# V1_input_channel_noNegSply_sch.net
KiCad netlist of a schematic drawn in Altium Designer
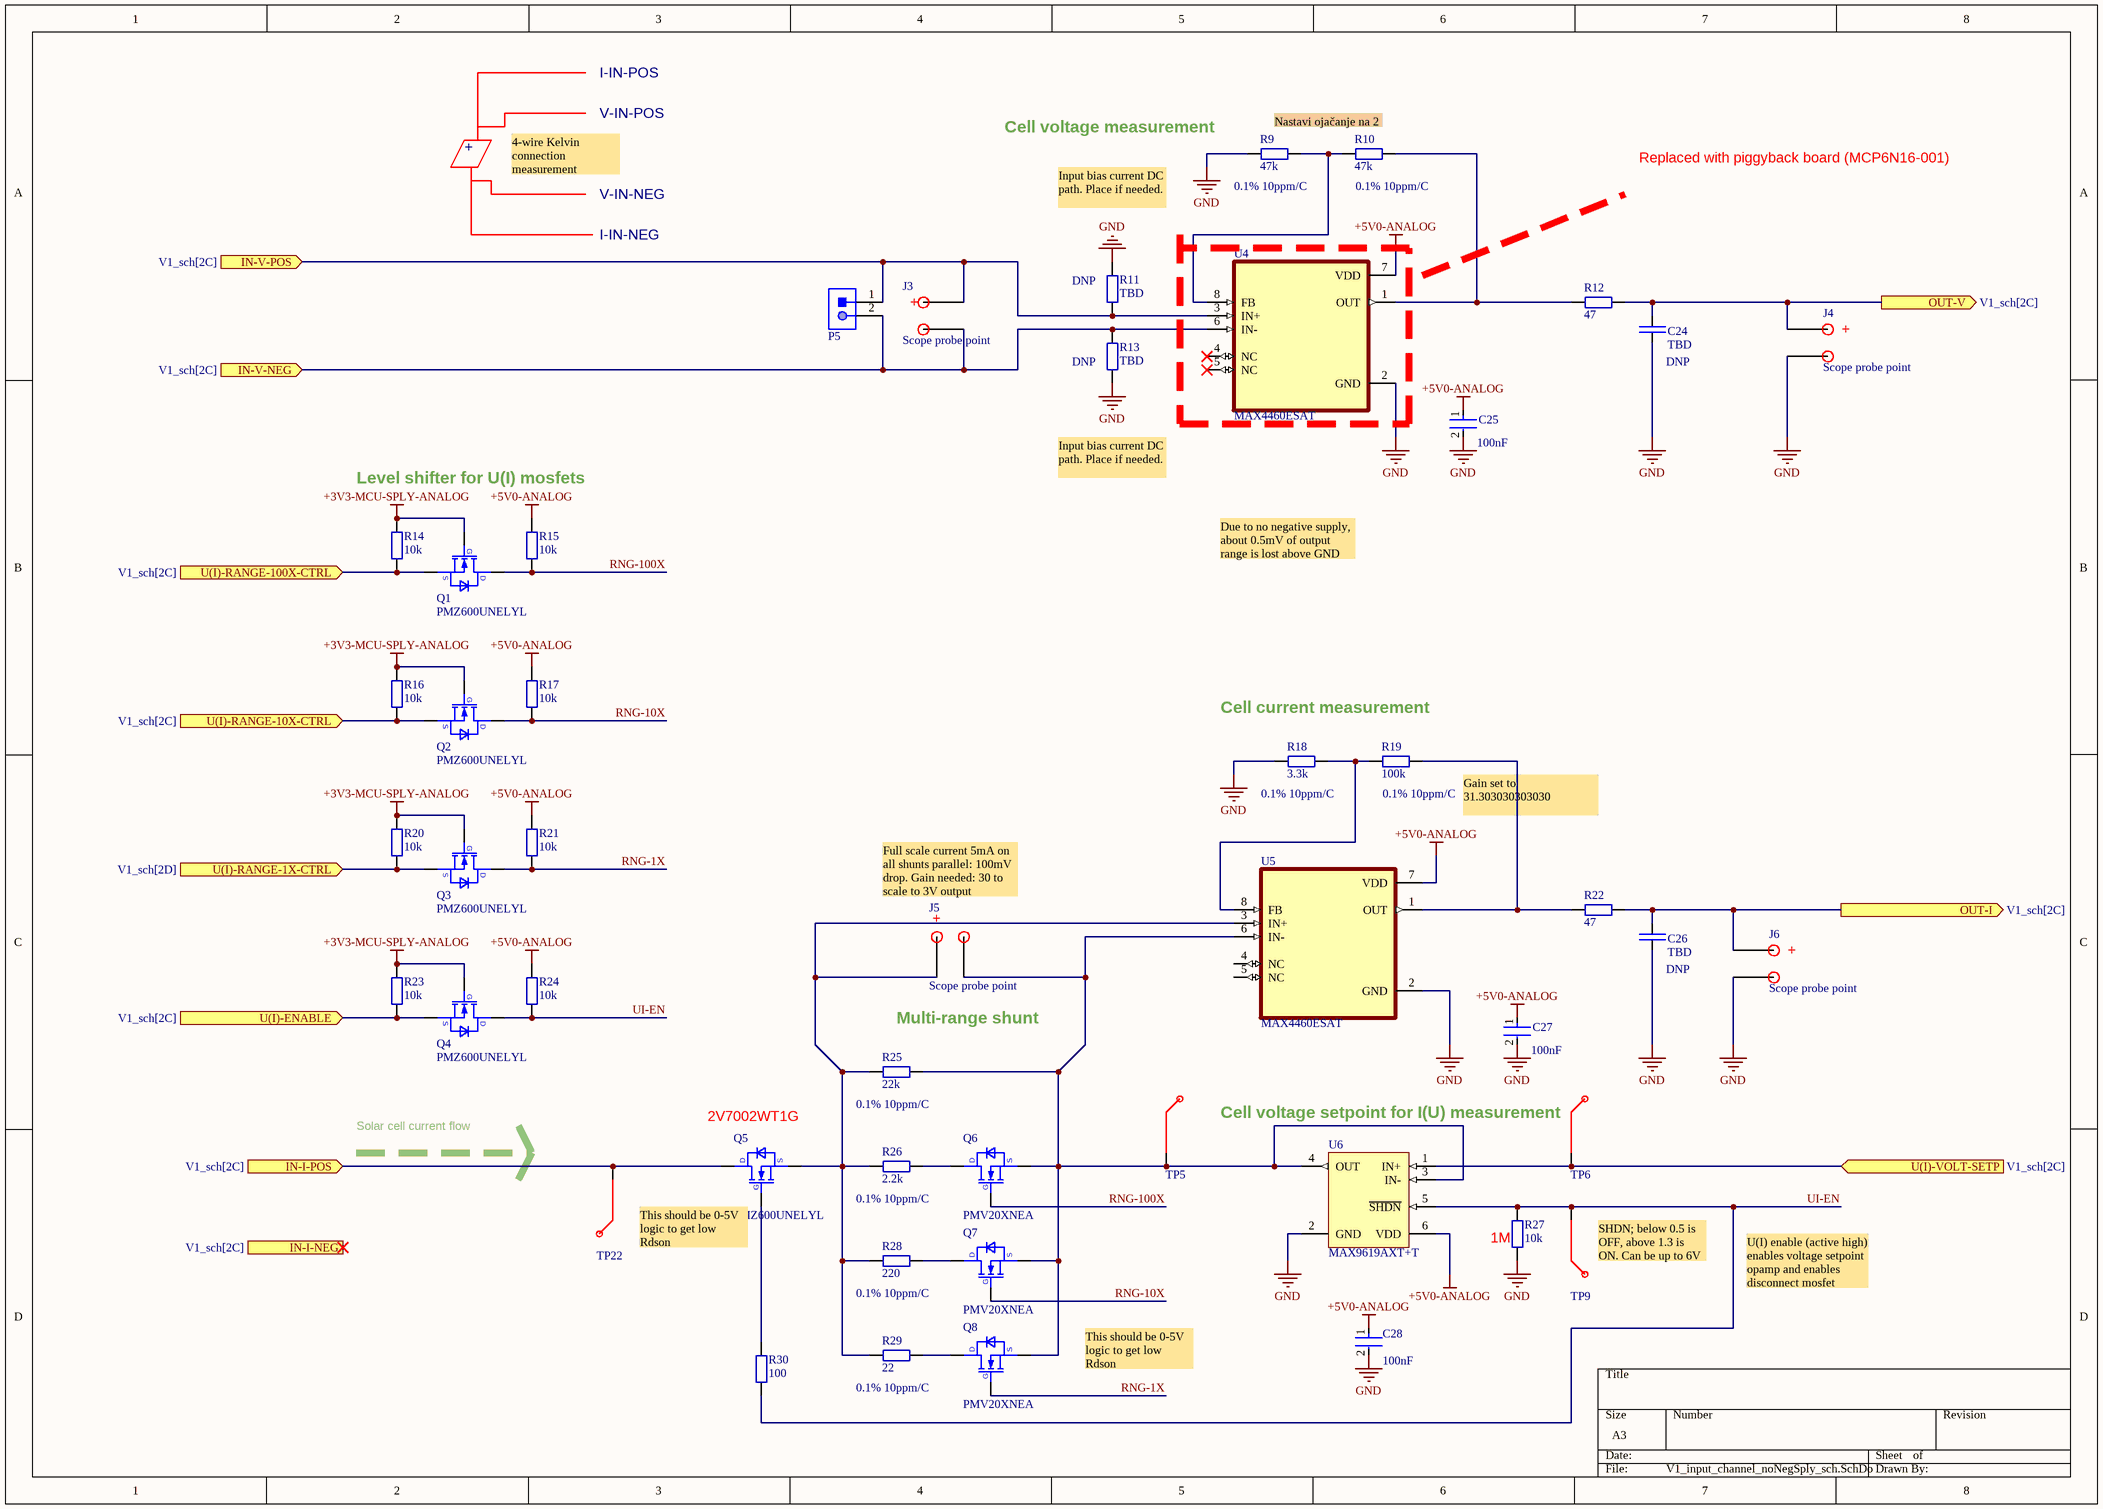
[diagram p0: V1_input_channel_noNegSply_sch.SchDoc]

(export (version "E")
  (design (tool "Eeschema 10.0.6"))
  (components
    (comp (ref "C24")
      (value "TBD")
      (footprint "Passives:FPR_0603_C_R0")
      (description "Capacitor - generic SMD")
      (fields (field (name "DNP") "DNP") (field (name "Comment") "PN_C0603_TBD"))
      (libsource (lib "Passives") (part "C"))
    )
    (comp (ref "C25")
      (value "885012206095")
      (footprint "FP-885012206095-IPC_B")
      (description "CAP CER 0.1UF 50V X7R 0603")
      (fields (field (name "TOLERANCE") "10%") (field (name "CAPACITANCE") "100nF"))
      (libsource (lib "Altium Content Vault") (part "11868f565c42a9108669ba33697ecf6"))
    )
    (comp (ref "C26")
      (value "TBD")
      (footprint "Passives:FPR_0603_C_R0")
      (description "Capacitor - generic SMD")
      (fields (field (name "DNP") "DNP") (field (name "Comment") "PN_C0603_TBD"))
      (libsource (lib "Passives") (part "C"))
    )
    (comp (ref "C27")
      (value "885012206095")
      (footprint "FP-885012206095-IPC_B")
      (description "CAP CER 0.1UF 50V X7R 0603")
      (fields (field (name "TOLERANCE") "10%") (field (name "CAPACITANCE") "100nF"))
      (libsource (lib "Altium Content Vault") (part "11868f565c42a9108669ba33697ecf6"))
    )
    (comp (ref "C28")
      (value "885012206095")
      (footprint "FP-885012206095-IPC_B")
      (description "CAP CER 0.1UF 50V X7R 0603")
      (fields (field (name "TOLERANCE") "10%") (field (name "CAPACITANCE") "100nF"))
      (libsource (lib "Altium Content Vault") (part "11868f565c42a9108669ba33697ecf6"))
    )
    (comp (ref "J3")
      (value "Scope probe point")
      (footprint "scope with ground spring probe point")
      (libsource (lib "") (part "Scope probe point_1"))
    )
    (comp (ref "J4")
      (value "Scope probe point")
      (footprint "scope with ground spring probe point")
      (libsource (lib "planinsekLib_sch") (part "Scope probe point"))
    )
    (comp (ref "J5")
      (value "Scope probe point")
      (footprint "scope with ground spring probe point")
      (libsource (lib "planinsekLib_sch") (part "Scope probe point"))
    )
    (comp (ref "J6")
      (value "Scope probe point")
      (footprint "scope with ground spring probe point")
      (libsource (lib "planinsekLib_sch") (part "Scope probe point"))
    )
    (comp (ref "P5")
      (value "61300211121")
      (footprint "61300211121")
      (description "THT Vertical Pin Header WR-PHD, Pitch 2.54 mm, Single Row, 2 pins")
      (fields (field (name "MANUFACTURER") "Wurth Elektronik") (field (name "PUBLISHER") "WurthElektronik"))
      (libsource (lib "Altium Content Vault") (part "WE-CN-1P-M-R2"))
    )
    (comp (ref "Q1")
      (value "PMZ600UNELYL")
      (footprint "DFN985X585X50-3N + SC-70 backup")
      (description "Low leakage N mosfet")
      (libsource (lib "nexperia_mosfets") (part "PMZ600UNELYL"))
    )
    (comp (ref "Q2")
      (value "PMZ600UNELYL")
      (footprint "DFN985X585X50-3N + SC-70 backup")
      (description "Low leakage N mosfet")
      (libsource (lib "nexperia_mosfets") (part "PMZ600UNELYL"))
    )
    (comp (ref "Q3")
      (value "PMZ600UNELYL")
      (footprint "DFN985X585X50-3N + SC-70 backup")
      (description "Low leakage N mosfet")
      (libsource (lib "nexperia_mosfets") (part "PMZ600UNELYL"))
    )
    (comp (ref "Q4")
      (value "PMZ600UNELYL")
      (footprint "DFN985X585X50-3N + SC-70 backup")
      (description "Low leakage N mosfet")
      (libsource (lib "nexperia_mosfets") (part "PMZ600UNELYL"))
    )
    (comp (ref "Q5")
      (value "PMZ600UNELYL")
      (footprint "DFN985X585X50-3N + SC-70 backup")
      (description "Low leakage N mosfet")
      (libsource (lib "nexperia_mosfets") (part "PMZ600UNELYL"))
    )
    (comp (ref "Q6")
      (value "PMV20XNEA")
      (footprint "SOT-23 for nexperia mosfets")
      (description "sot-23 N mosfet low Rdson")
      (libsource (lib "nexperia_mosfets") (part "PMV20XNEA"))
    )
    (comp (ref "Q7")
      (value "PMV20XNEA")
      (footprint "SOT-23 for nexperia mosfets")
      (description "sot-23 N mosfet low Rdson")
      (libsource (lib "nexperia_mosfets") (part "PMV20XNEA"))
    )
    (comp (ref "Q8")
      (value "PMV20XNEA")
      (footprint "SOT-23 for nexperia mosfets")
      (description "sot-23 N mosfet low Rdson")
      (libsource (lib "nexperia_mosfets") (part "PMV20XNEA"))
    )
    (comp (ref "R9")
      (value "47k")
      (footprint "Passives:FPR_0603_R_R0")
      (description "Resistor - generic SMD")
      (fields (field (name "TOLERANCE") "0.1% 10ppm/C") (field (name "Comment") "PN_R0603_47k_0%1_10ppm"))
      (libsource (lib "Passives") (part "R"))
    )
    (comp (ref "R10")
      (value "47k")
      (footprint "Passives:FPR_0603_R_R0")
      (description "Resistor - generic SMD")
      (fields (field (name "TOLERANCE") "0.1% 10ppm/C") (field (name "Comment") "PN_R0603_47k_0%1_10ppm"))
      (libsource (lib "Passives") (part "R"))
    )
    (comp (ref "R11")
      (value "TBD")
      (footprint "Passives:FPR_0805_R_R0")
      (description "Resistor - generic SMD")
      (fields (field (name "DNP") "DNP") (field (name "Comment") "PN_R0603_TBD"))
      (libsource (lib "Passives") (part "R"))
    )
    (comp (ref "R12")
      (value "47")
      (footprint "Passives:FPR_0603_R_R0")
      (description "Resistor - generic SMD")
      (fields (field (name "Comment") "PN_R0603_TBD"))
      (libsource (lib "Passives") (part "R"))
    )
    (comp (ref "R13")
      (value "TBD")
      (footprint "Passives:FPR_0805_R_R0")
      (description "Resistor - generic SMD")
      (fields (field (name "DNP") "DNP") (field (name "Comment") "PN_R0603_TBD"))
      (libsource (lib "Passives") (part "R"))
    )
    (comp (ref "R14")
      (value "10k")
      (footprint "Passives:FPR_0603_R_R0")
      (description "Resistor - generic SMD")
      (fields (field (name "Comment") "PN_R0603_10k"))
      (libsource (lib "Passives") (part "R"))
    )
    (comp (ref "R15")
      (value "10k")
      (footprint "Passives:FPR_0603_R_R0")
      (description "Resistor - generic SMD")
      (fields (field (name "Comment") "PN_R0603_10k"))
      (libsource (lib "Passives") (part "R"))
    )
    (comp (ref "R16")
      (value "10k")
      (footprint "Passives:FPR_0603_R_R0")
      (description "Resistor - generic SMD")
      (fields (field (name "Comment") "PN_R0603_10k"))
      (libsource (lib "Passives") (part "R"))
    )
    (comp (ref "R17")
      (value "10k")
      (footprint "Passives:FPR_0603_R_R0")
      (description "Resistor - generic SMD")
      (fields (field (name "Comment") "PN_R0603_10k"))
      (libsource (lib "Passives") (part "R"))
    )
    (comp (ref "R18")
      (value "3.3k")
      (footprint "Passives:FPR_0603_R_R0")
      (description "Resistor - generic SMD")
      (fields (field (name "TOLERANCE") "0.1% 10ppm/C") (field (name "Comment") "PN_R0603_3k3_0%1_10ppm"))
      (libsource (lib "Passives") (part "R"))
    )
    (comp (ref "R19")
      (value "100k")
      (footprint "Passives:FPR_0603_R_R0")
      (description "Resistor - generic SMD")
      (fields (field (name "TOLERANCE") "0.1% 10ppm/C") (field (name "Comment") "PN_R0603_100k_0%1_10ppm"))
      (libsource (lib "Passives") (part "R"))
    )
    (comp (ref "R20")
      (value "10k")
      (footprint "Passives:FPR_0603_R_R0")
      (description "Resistor - generic SMD")
      (fields (field (name "Comment") "PN_R0603_10k"))
      (libsource (lib "Passives") (part "R"))
    )
    (comp (ref "R21")
      (value "10k")
      (footprint "Passives:FPR_0603_R_R0")
      (description "Resistor - generic SMD")
      (fields (field (name "Comment") "PN_R0603_10k"))
      (libsource (lib "Passives") (part "R"))
    )
    (comp (ref "R22")
      (value "47")
      (footprint "Passives:FPR_0603_R_R0")
      (description "Resistor - generic SMD")
      (fields (field (name "Comment") "PN_R0603_TBD"))
      (libsource (lib "Passives") (part "R"))
    )
    (comp (ref "R23")
      (value "10k")
      (footprint "Passives:FPR_0603_R_R0")
      (description "Resistor - generic SMD")
      (fields (field (name "Comment") "PN_R0603_10k"))
      (libsource (lib "Passives") (part "R"))
    )
    (comp (ref "R24")
      (value "10k")
      (footprint "Passives:FPR_0603_R_R0")
      (description "Resistor - generic SMD")
      (fields (field (name "Comment") "PN_R0603_10k"))
      (libsource (lib "Passives") (part "R"))
    )
    (comp (ref "R25")
      (value "22k")
      (footprint "Passives:FPR_0603_R_R0")
      (description "Resistor - generic SMD")
      (fields (field (name "TOLERANCE") "0.1% 10ppm/C") (field (name "Comment") "PN_R0603_22K_0%1_10ppm"))
      (libsource (lib "Passives") (part "R"))
    )
    (comp (ref "R26")
      (value "2.2k")
      (footprint "Passives:FPR_0603_R_R0")
      (description "Resistor - generic SMD")
      (fields (field (name "TOLERANCE") "0.1% 10ppm/C") (field (name "Comment") "PN_R0603_2K2_0%1_10ppm"))
      (libsource (lib "Passives") (part "R"))
    )
    (comp (ref "R27")
      (value "10k")
      (footprint "Passives:FPR_0603_R_R0")
      (description "Resistor - generic SMD")
      (fields (field (name "Comment") "PN_R0603_10k"))
      (libsource (lib "Passives") (part "R"))
    )
    (comp (ref "R28")
      (value "220")
      (footprint "Passives:FPR_0603_R_R0")
      (description "Resistor - generic SMD")
      (fields (field (name "TOLERANCE") "0.1% 10ppm/C") (field (name "Comment") "PN_R0603_220R_0%1_10ppm"))
      (libsource (lib "Passives") (part "R"))
    )
    (comp (ref "R29")
      (value "22")
      (footprint "Passives:FPR_0603_R_R0")
      (description "Resistor - generic SMD")
      (fields (field (name "TOLERANCE") "0.1% 10ppm/C") (field (name "Comment") "PN_R0603_22R_0%1_10ppm"))
      (libsource (lib "Passives") (part "R"))
    )
    (comp (ref "R30")
      (value "100")
      (footprint "Passives:FPR_0603_R_R0")
      (description "Resistor - generic SMD")
      (fields (field (name "Comment") "PN_R0603_100R"))
      (libsource (lib "Passives") (part "R"))
    )
    (comp (ref "TP5")
      (value "Test Point")
      (footprint "Test Point 1.5mm SMD")
      (libsource (lib "planinsekLib_sch") (part "Test Point"))
    )
    (comp (ref "TP6")
      (value "Test Point")
      (footprint "Test Point 1.5mm SMD")
      (libsource (lib "planinsekLib_sch") (part "Test Point"))
    )
    (comp (ref "TP9")
      (value "Test Point")
      (footprint "Test Point 1.5mm SMD")
      (libsource (lib "planinsekLib_sch") (part "Test Point"))
    )
    (comp (ref "TP22")
      (value "Test Point")
      (footprint "Test Point 1.5mm SMD")
      (libsource (lib "planinsekLib_sch") (part "Test Point"))
    )
    (comp (ref "U4")
      (value "MAX4460ESAT")
      (footprint "SOIC127P600X175-8N")
      (libsource (lib "MAX4460ESAT") (part "MAX4460ESAT"))
    )
    (comp (ref "U5")
      (value "MAX4460ESAT")
      (footprint "SOIC127P600X175-8N")
      (libsource (lib "MAX4460ESAT") (part "MAX4460ESAT"))
    )
    (comp (ref "U6")
      (value "MAX9619AXT+T")
      (footprint "X6SN+1_N")
      (libsource (lib "Altium Content Vault") (part "AMP-OPA-MAX9619-IL6"))
    )
  )
  (nets
    (net (code "1") (name "+3V3-MCU-SPLY-ANALOG") (class "Default")
      (node (ref "Q1") (pin "1") (pinfunction "GATE_1") (pintype "passive"))
      (node (ref "Q2") (pin "1") (pinfunction "GATE_1") (pintype "passive"))
      (node (ref "Q3") (pin "1") (pinfunction "GATE_1") (pintype "passive"))
      (node (ref "Q4") (pin "1") (pinfunction "GATE_1") (pintype "passive"))
      (node (ref "R14") (pin "2") (pinfunction "2_2") (pintype "passive"))
      (node (ref "R16") (pin "2") (pinfunction "2_2") (pintype "passive"))
      (node (ref "R20") (pin "2") (pinfunction "2_2") (pintype "passive"))
      (node (ref "R23") (pin "2") (pinfunction "2_2") (pintype "passive"))
    )
    (net (code "2") (name "+5V0-ANALOG") (class "Default")
      (node (ref "C25") (pin "1") (pinfunction "1_1") (pintype "passive"))
      (node (ref "C27") (pin "1") (pinfunction "1_1") (pintype "passive"))
      (node (ref "C28") (pin "1") (pinfunction "1_1") (pintype "passive"))
      (node (ref "R15") (pin "2") (pinfunction "2_2") (pintype "passive"))
      (node (ref "R17") (pin "2") (pinfunction "2_2") (pintype "passive"))
      (node (ref "R21") (pin "2") (pinfunction "2_2") (pintype "passive"))
      (node (ref "R24") (pin "2") (pinfunction "2_2") (pintype "passive"))
      (node (ref "U4") (pin "7") (pinfunction "VDD_7") (pintype "power_in"))
      (node (ref "U5") (pin "7") (pinfunction "VDD_7") (pintype "power_in"))
      (node (ref "U6") (pin "6") (pinfunction "VDD_6") (pintype "power_in"))
    )
    (net (code "4") (name "/IN-I-POS") (class "Default")
      (node (ref "Q5") (pin "3") (pinfunction "DRAIN_3") (pintype "passive"))
      (node (ref "TP22") (pin "1") (pintype "passive"))
    )
    (net (code "5") (name "/IN-V-NEG") (class "Default")
      (node (ref "J3") (pin "NEG") (pinfunction "NEG_NEG") (pintype "passive"))
      (node (ref "P5") (pin "2") (pinfunction "2_2") (pintype "passive"))
      (node (ref "R13") (pin "2") (pinfunction "2_2") (pintype "passive"))
      (node (ref "U4") (pin "6") (pinfunction "IN-_6") (pintype "input"))
    )
    (net (code "6") (name "/IN-V-POS") (class "Default")
      (node (ref "J3") (pin "POS") (pinfunction "POS_POS") (pintype "passive"))
      (node (ref "P5") (pin "1") (pinfunction "1_1") (pintype "passive"))
      (node (ref "R11") (pin "1") (pinfunction "1_1") (pintype "passive"))
      (node (ref "U4") (pin "3") (pinfunction "IN+_3") (pintype "input"))
    )
    (net (code "7") (name "/OUT-I") (class "Default")
      (node (ref "C26") (pin "2") (pinfunction "2_2") (pintype "passive"))
      (node (ref "J6") (pin "POS") (pinfunction "POS_POS") (pintype "passive"))
      (node (ref "R22") (pin "1") (pinfunction "1_1") (pintype "passive"))
    )
    (net (code "8") (name "/OUT-V") (class "Default")
      (node (ref "C24") (pin "2") (pinfunction "2_2") (pintype "passive"))
      (node (ref "J4") (pin "POS") (pinfunction "POS_POS") (pintype "passive"))
      (node (ref "R12") (pin "1") (pinfunction "1_1") (pintype "passive"))
    )
    (net (code "9") (name "/RNG-1X") (class "Default")
      (node (ref "Q3") (pin "3") (pinfunction "DRAIN_3") (pintype "passive"))
      (node (ref "Q8") (pin "1") (pinfunction "GATE_1") (pintype "passive"))
      (node (ref "R21") (pin "1") (pinfunction "1_1") (pintype "passive"))
    )
    (net (code "10") (name "/RNG-10X") (class "Default")
      (node (ref "Q2") (pin "3") (pinfunction "DRAIN_3") (pintype "passive"))
      (node (ref "Q7") (pin "1") (pinfunction "GATE_1") (pintype "passive"))
      (node (ref "R17") (pin "1") (pinfunction "1_1") (pintype "passive"))
    )
    (net (code "11") (name "/RNG-100X") (class "Default")
      (node (ref "Q1") (pin "3") (pinfunction "DRAIN_3") (pintype "passive"))
      (node (ref "Q6") (pin "1") (pinfunction "GATE_1") (pintype "passive"))
      (node (ref "R15") (pin "1") (pinfunction "1_1") (pintype "passive"))
    )
    (net (code "12") (name "/U(I)-ENABLE") (class "Default")
      (node (ref "Q4") (pin "2") (pinfunction "SOURCE_2") (pintype "passive"))
      (node (ref "R23") (pin "1") (pinfunction "1_1") (pintype "passive"))
    )
    (net (code "13") (name "/U(I)-RANGE-1X-CTRL") (class "Default")
      (node (ref "Q3") (pin "2") (pinfunction "SOURCE_2") (pintype "passive"))
      (node (ref "R20") (pin "1") (pinfunction "1_1") (pintype "passive"))
    )
    (net (code "14") (name "/U(I)-RANGE-10X-CTRL") (class "Default")
      (node (ref "Q2") (pin "2") (pinfunction "SOURCE_2") (pintype "passive"))
      (node (ref "R16") (pin "1") (pinfunction "1_1") (pintype "passive"))
    )
    (net (code "15") (name "/U(I)-RANGE-100X-CTRL") (class "Default")
      (node (ref "Q1") (pin "2") (pinfunction "SOURCE_2") (pintype "passive"))
      (node (ref "R14") (pin "1") (pinfunction "1_1") (pintype "passive"))
    )
    (net (code "16") (name "/U(I)-VOLT-SETP") (class "Default")
      (node (ref "TP6") (pin "1") (pintype "passive"))
      (node (ref "U6") (pin "1") (pinfunction "IN+_1") (pintype "input"))
    )
    (net (code "17") (name "/UI-EN") (class "Default")
      (node (ref "Q4") (pin "3") (pinfunction "DRAIN_3") (pintype "passive"))
      (node (ref "R24") (pin "1") (pinfunction "1_1") (pintype "passive"))
      (node (ref "R27") (pin "2") (pinfunction "2_2") (pintype "passive"))
      (node (ref "R30") (pin "1") (pinfunction "1_1") (pintype "passive"))
      (node (ref "TP9") (pin "1") (pintype "passive"))
      (node (ref "U6") (pin "5") (pinfunction "~{SHDN}_5") (pintype "input"))
    )
    (net (code "18") (name "GND") (class "Default")
      (node (ref "C24") (pin "1") (pinfunction "1_1") (pintype "passive"))
      (node (ref "C25") (pin "2") (pinfunction "2_2") (pintype "passive"))
      (node (ref "C26") (pin "1") (pinfunction "1_1") (pintype "passive"))
      (node (ref "C27") (pin "2") (pinfunction "2_2") (pintype "passive"))
      (node (ref "C28") (pin "2") (pinfunction "2_2") (pintype "passive"))
      (node (ref "J4") (pin "NEG") (pinfunction "NEG_NEG") (pintype "passive"))
      (node (ref "J6") (pin "NEG") (pinfunction "NEG_NEG") (pintype "passive"))
      (node (ref "R11") (pin "2") (pinfunction "2_2") (pintype "passive"))
      (node (ref "R13") (pin "1") (pinfunction "1_1") (pintype "passive"))
      (node (ref "R18") (pin "2") (pinfunction "2_2") (pintype "passive"))
      (node (ref "R27") (pin "1") (pinfunction "1_1") (pintype "passive"))
      (node (ref "R9") (pin "2") (pinfunction "2_2") (pintype "passive"))
      (node (ref "U4") (pin "2") (pinfunction "GND_2") (pintype "power_in"))
      (node (ref "U5") (pin "2") (pinfunction "GND_2") (pintype "power_in"))
      (node (ref "U6") (pin "2") (pinfunction "GND_2") (pintype "power_in"))
    )
    (net (code "19") (name "Net-(Q5-GATE)") (class "Default")
      (node (ref "Q5") (pin "1") (pinfunction "GATE_1") (pintype "passive"))
      (node (ref "R30") (pin "2") (pinfunction "2_2") (pintype "passive"))
    )
    (net (code "20") (name "Net-(Q5-SOURCE)") (class "Default")
      (node (ref "J5") (pin "POS") (pinfunction "POS_POS") (pintype "passive"))
      (node (ref "Q5") (pin "2") (pinfunction "SOURCE_2") (pintype "passive"))
      (node (ref "R25") (pin "2") (pinfunction "2_2") (pintype "passive"))
      (node (ref "R26") (pin "2") (pinfunction "2_2") (pintype "passive"))
      (node (ref "R28") (pin "2") (pinfunction "2_2") (pintype "passive"))
      (node (ref "R29") (pin "2") (pinfunction "2_2") (pintype "passive"))
      (node (ref "U5") (pin "3") (pinfunction "IN+_3") (pintype "input"))
    )
    (net (code "21") (name "Net-(Q6-DRAIN)") (class "Default")
      (node (ref "Q6") (pin "3") (pinfunction "DRAIN_3") (pintype "passive"))
      (node (ref "R26") (pin "1") (pinfunction "1_1") (pintype "passive"))
    )
    (net (code "22") (name "Net-(Q6-SOURCE)") (class "Default")
      (node (ref "J5") (pin "NEG") (pinfunction "NEG_NEG") (pintype "passive"))
      (node (ref "Q6") (pin "2") (pinfunction "SOURCE_2") (pintype "passive"))
      (node (ref "Q7") (pin "2") (pinfunction "SOURCE_2") (pintype "passive"))
      (node (ref "Q8") (pin "2") (pinfunction "SOURCE_2") (pintype "passive"))
      (node (ref "R25") (pin "1") (pinfunction "1_1") (pintype "passive"))
      (node (ref "TP5") (pin "1") (pintype "passive"))
      (node (ref "U5") (pin "6") (pinfunction "IN-_6") (pintype "input"))
      (node (ref "U6") (pin "3") (pinfunction "IN-_3") (pintype "input"))
      (node (ref "U6") (pin "4") (pinfunction "OUT_4") (pintype "output"))
    )
    (net (code "23") (name "Net-(Q7-DRAIN)") (class "Default")
      (node (ref "Q7") (pin "3") (pinfunction "DRAIN_3") (pintype "passive"))
      (node (ref "R28") (pin "1") (pinfunction "1_1") (pintype "passive"))
    )
    (net (code "24") (name "Net-(Q8-DRAIN)") (class "Default")
      (node (ref "Q8") (pin "3") (pinfunction "DRAIN_3") (pintype "passive"))
      (node (ref "R29") (pin "1") (pinfunction "1_1") (pintype "passive"))
    )
    (net (code "25") (name "Net-(U4-FB)") (class "Default")
      (node (ref "R10") (pin "2") (pinfunction "2_2") (pintype "passive"))
      (node (ref "R9") (pin "1") (pinfunction "1_1") (pintype "passive"))
      (node (ref "U4") (pin "8") (pinfunction "FB_8") (pintype "input"))
    )
    (net (code "26") (name "Net-(U4-OUT)") (class "Default")
      (node (ref "R10") (pin "1") (pinfunction "1_1") (pintype "passive"))
      (node (ref "R12") (pin "2") (pinfunction "2_2") (pintype "passive"))
      (node (ref "U4") (pin "1") (pinfunction "OUT_1") (pintype "output"))
    )
    (net (code "27") (name "Net-(U5-FB)") (class "Default")
      (node (ref "R18") (pin "1") (pinfunction "1_1") (pintype "passive"))
      (node (ref "R19") (pin "2") (pinfunction "2_2") (pintype "passive"))
      (node (ref "U5") (pin "8") (pinfunction "FB_8") (pintype "input"))
    )
    (net (code "28") (name "Net-(U5-OUT)") (class "Default")
      (node (ref "R19") (pin "1") (pinfunction "1_1") (pintype "passive"))
      (node (ref "R22") (pin "2") (pinfunction "2_2") (pintype "passive"))
      (node (ref "U5") (pin "1") (pinfunction "OUT_1") (pintype "output"))
    )
    (net (code "29") (name "unconnected-(U4-NC-Pad4)") (class "Default")
      (node (ref "U4") (pin "4") (pinfunction "NC_4") (pintype "bidirectional+no_connect"))
    )
    (net (code "30") (name "unconnected-(U4-NC-Pad5)") (class "Default")
      (node (ref "U4") (pin "5") (pinfunction "NC_5") (pintype "bidirectional+no_connect"))
    )
    (net (code "31") (name "unconnected-(U5-NC-Pad4)") (class "Default")
      (node (ref "U5") (pin "4") (pinfunction "NC_4") (pintype "bidirectional"))
    )
    (net (code "32") (name "unconnected-(U5-NC-Pad5)") (class "Default")
      (node (ref "U5") (pin "5") (pinfunction "NC_5") (pintype "bidirectional"))
    )
  )
)
